# SCH_NeuroMems_V2_10_2025-06-07.net
KiCad netlist of a schematic drawn in EasyEDA
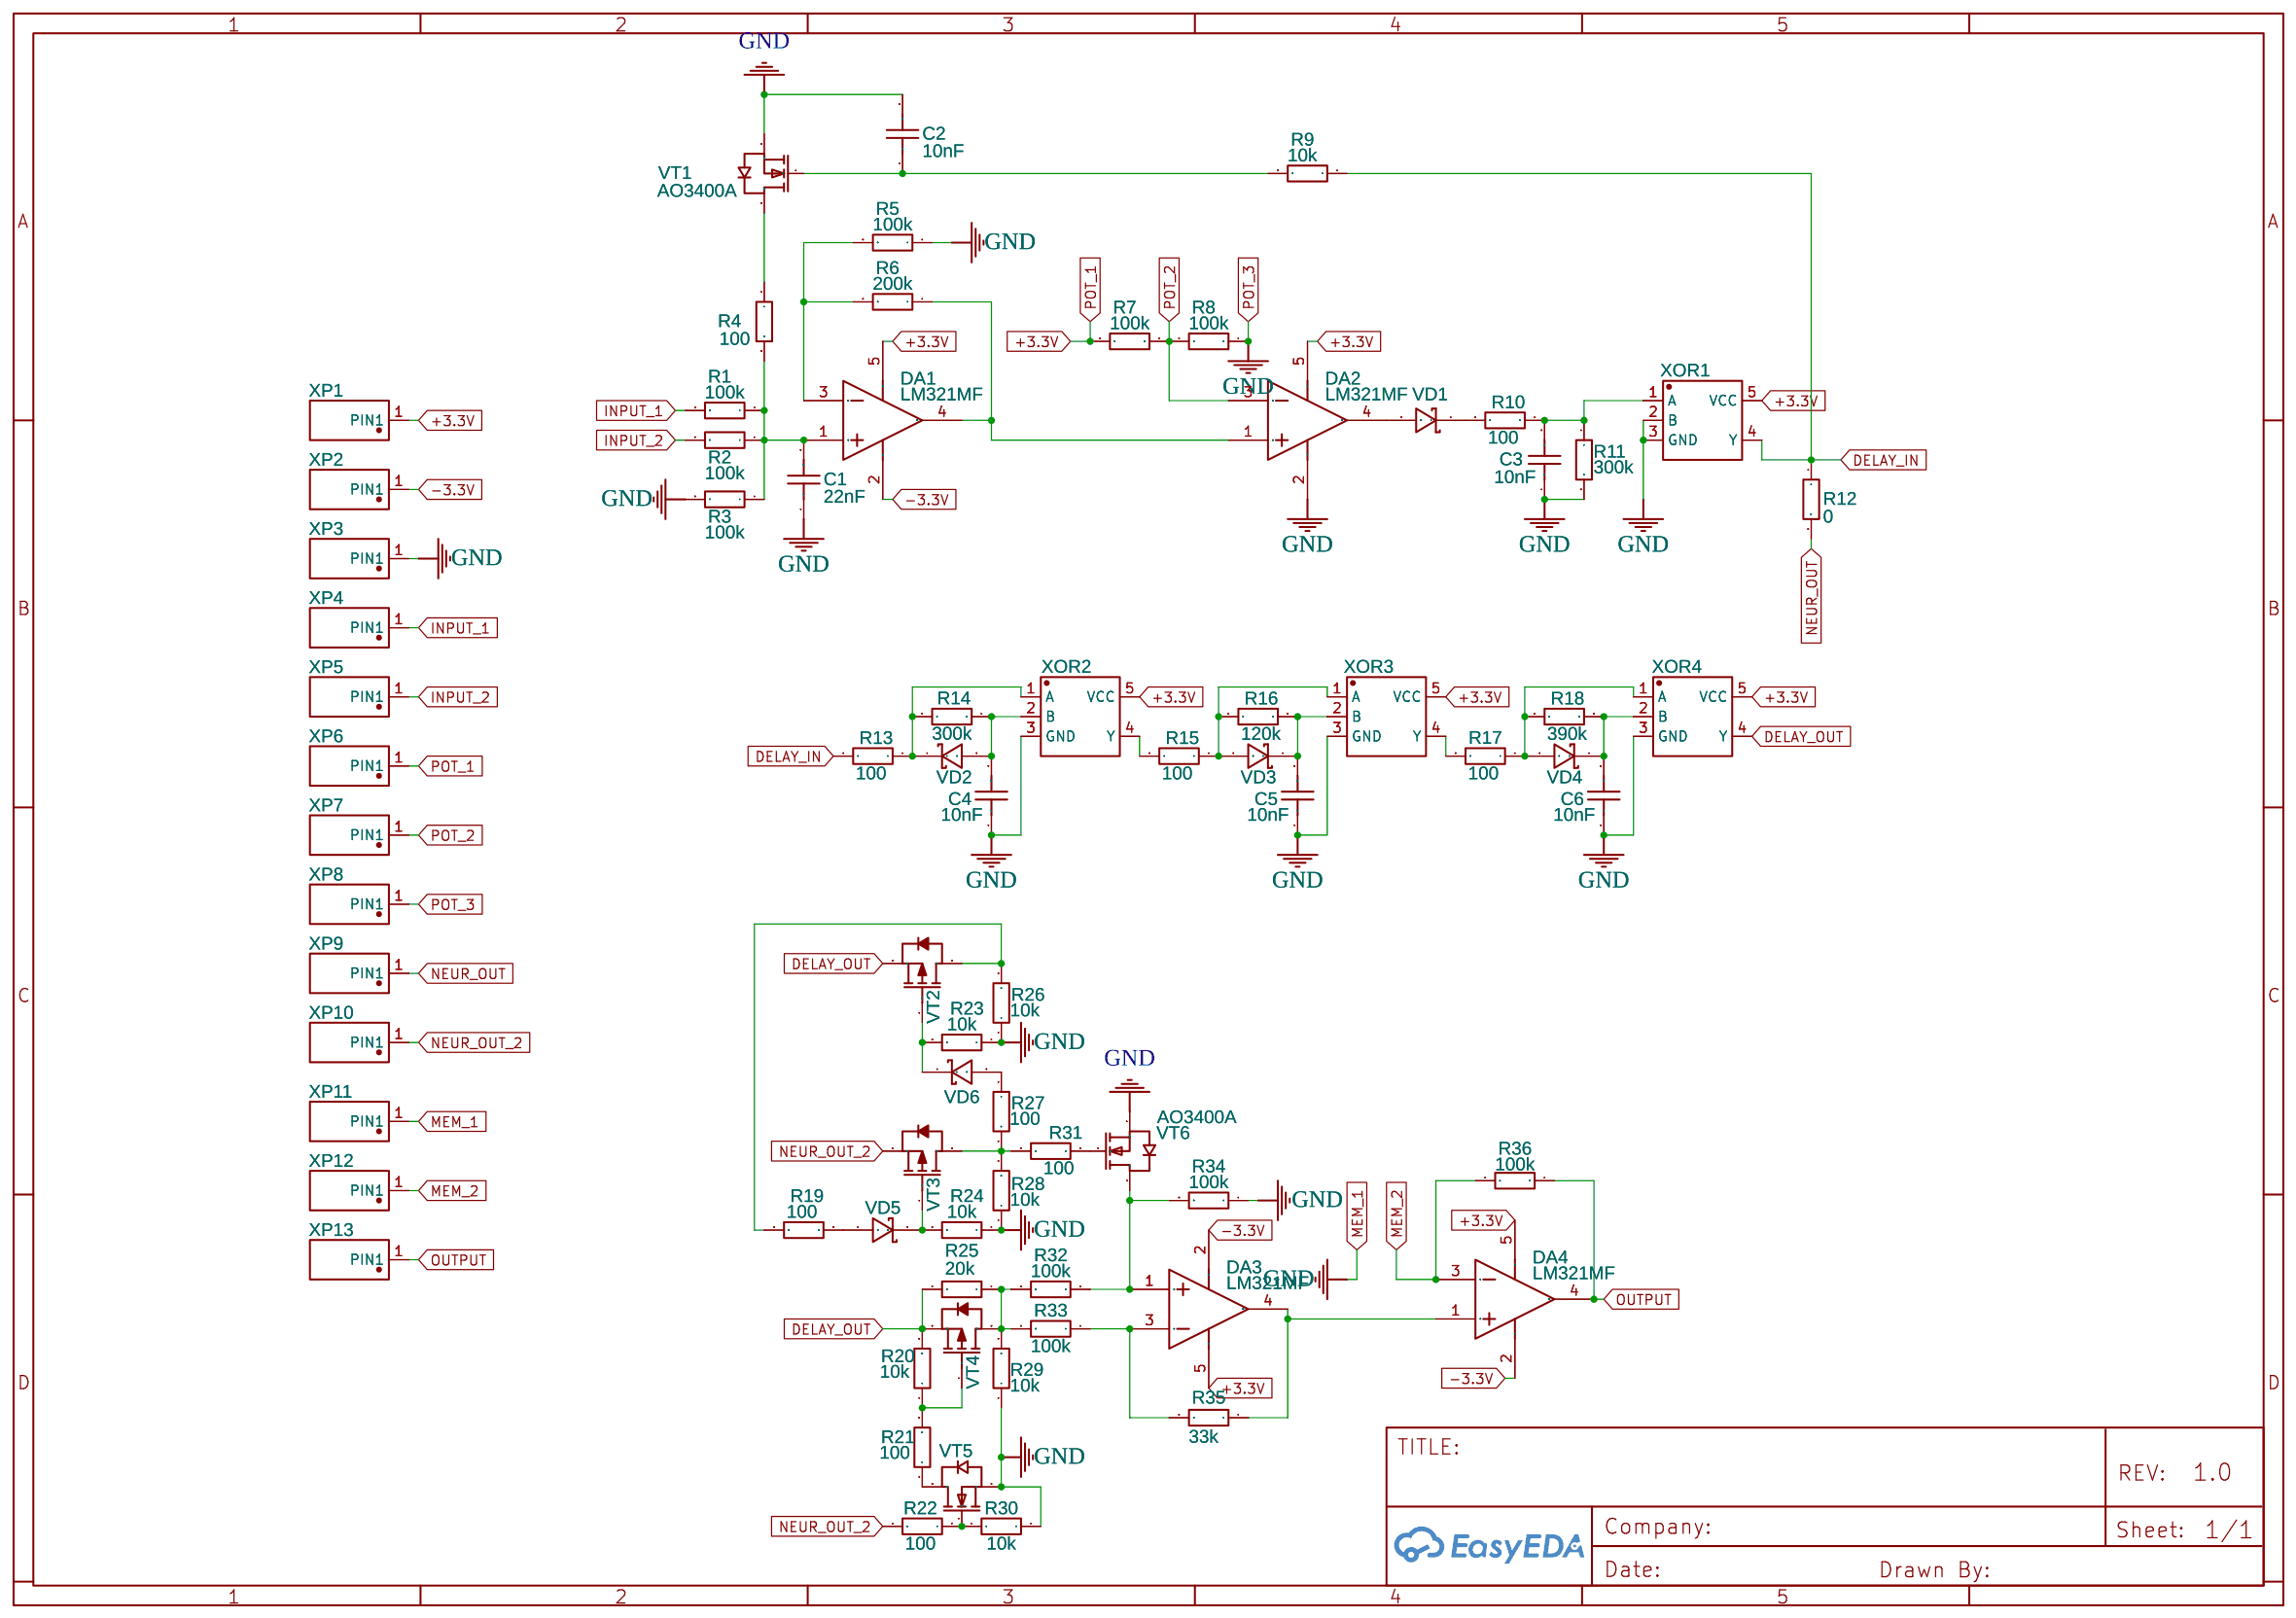
[diagram p0: schematic sheet]

(export (version "E")
  (design (tool "Eeschema 10.0.6"))
  (components
    (comp (ref "C1")
      (value "22nF")
      (fields (field (name "Manufacturer Part") "GRM155R71E103KA01D | SMD Ceramic Capacitor"))
      (libsource (lib "") (part "GRM155R71E103KA01D | SMD CERAMIC CAPACITOR"))
    )
    (comp (ref "C2")
      (value "10nF")
      (fields (field (name "Manufacturer Part") "0201"))
      (libsource (lib "") (part "0201_C9900015864"))
    )
    (comp (ref "C3")
      (value "10nF")
      (fields (field (name "Manufacturer Part") "GRM155R71E103KA01D | SMD Ceramic Capacitor"))
      (libsource (lib "") (part "GRM155R71E103KA01D | SMD CERAMIC CAPACITOR"))
    )
    (comp (ref "C4")
      (value "10nF")
      (fields (field (name "Manufacturer Part") "GRM155R71E103KA01D | SMD Ceramic Capacitor"))
      (libsource (lib "") (part "GRM155R71E103KA01D | SMD CERAMIC CAPACITOR"))
    )
    (comp (ref "C5")
      (value "10nF")
      (fields (field (name "Manufacturer Part") "GRM155R71E103KA01D | SMD Ceramic Capacitor"))
      (libsource (lib "") (part "GRM155R71E103KA01D | SMD CERAMIC CAPACITOR"))
    )
    (comp (ref "C6")
      (value "10nF")
      (fields (field (name "Manufacturer Part") "GRM155R71E103KA01D | SMD Ceramic Capacitor"))
      (libsource (lib "") (part "GRM155R71E103KA01D | SMD CERAMIC CAPACITOR"))
    )
    (comp (ref "DA1")
      (value "LM321MF")
      (fields (field (name "Manufacturer Part") "LM321MF/NOPB") (field (name "Manufacturer") "TI(德州仪器)"))
      (libsource (lib "") (part "LM321MF/NOPB"))
    )
    (comp (ref "DA2")
      (value "LM321MF")
      (fields (field (name "Manufacturer Part") "LM321MF/NOPB") (field (name "Manufacturer") "TI(德州仪器)"))
      (libsource (lib "") (part "LM321MF/NOPB"))
    )
    (comp (ref "DA3")
      (value "LM321MF")
      (fields (field (name "Manufacturer Part") "LM321MF/NOPB") (field (name "Manufacturer") "TI(德州仪器)"))
      (libsource (lib "") (part "LM321MF/NOPB_1"))
    )
    (comp (ref "DA4")
      (value "LM321MF")
      (fields (field (name "Manufacturer Part") "LM321MF/NOPB") (field (name "Manufacturer") "TI(德州仪器)"))
      (libsource (lib "") (part "LM321MF/NOPB"))
    )
    (comp (ref "R1")
      (value "100k")
      (fields (field (name "Manufacturer Part") "0201"))
      (libsource (lib "") (part "0201"))
    )
    (comp (ref "R2")
      (value "100k")
      (fields (field (name "Manufacturer Part") "0201"))
      (libsource (lib "") (part "0201"))
    )
    (comp (ref "R3")
      (value "100k")
      (fields (field (name "Manufacturer Part") "0201"))
      (libsource (lib "") (part "0201"))
    )
    (comp (ref "R4")
      (value "100")
      (fields (field (name "Manufacturer Part") "0201"))
      (libsource (lib "") (part "0201_3"))
    )
    (comp (ref "R5")
      (value "100k")
      (fields (field (name "Manufacturer Part") "0201"))
      (libsource (lib "") (part "0201"))
    )
    (comp (ref "R6")
      (value "200k")
      (fields (field (name "Manufacturer Part") "0201"))
      (libsource (lib "") (part "0201"))
    )
    (comp (ref "R7")
      (value "100k")
      (fields (field (name "Manufacturer Part") "0201"))
      (libsource (lib "") (part "0201"))
    )
    (comp (ref "R8")
      (value "100k")
      (fields (field (name "Manufacturer Part") "0201"))
      (libsource (lib "") (part "0201"))
    )
    (comp (ref "R9")
      (value "10k")
      (fields (field (name "Manufacturer Part") "0201"))
      (libsource (lib "") (part "0201"))
    )
    (comp (ref "R10")
      (value "100")
      (fields (field (name "Manufacturer Part") "0201"))
      (libsource (lib "") (part "0201"))
    )
    (comp (ref "R11")
      (value "300k")
      (fields (field (name "Manufacturer Part") "0201"))
      (libsource (lib "") (part "0201_3"))
    )
    (comp (ref "R12")
      (value "0")
      (fields (field (name "Manufacturer Part") "0201"))
      (libsource (lib "") (part "0201_3"))
    )
    (comp (ref "R13")
      (value "100")
      (fields (field (name "Manufacturer Part") "0201"))
      (libsource (lib "") (part "0201"))
    )
    (comp (ref "R14")
      (value "300k")
      (fields (field (name "Manufacturer Part") "0201"))
      (libsource (lib "") (part "0201"))
    )
    (comp (ref "R15")
      (value "100")
      (fields (field (name "Manufacturer Part") "0201"))
      (libsource (lib "") (part "0201"))
    )
    (comp (ref "R16")
      (value "120k")
      (fields (field (name "Manufacturer Part") "0201"))
      (libsource (lib "") (part "0201"))
    )
    (comp (ref "R17")
      (value "100")
      (fields (field (name "Manufacturer Part") "0201"))
      (libsource (lib "") (part "0201"))
    )
    (comp (ref "R18")
      (value "390k")
      (fields (field (name "Manufacturer Part") "0201"))
      (libsource (lib "") (part "0201"))
    )
    (comp (ref "R19")
      (value "100")
      (fields (field (name "Manufacturer Part") "0201"))
      (libsource (lib "") (part "0201_2"))
    )
    (comp (ref "R20")
      (value "10k")
      (fields (field (name "Manufacturer Part") "0201"))
      (libsource (lib "") (part "0201_1"))
    )
    (comp (ref "R21")
      (value "100")
      (fields (field (name "Manufacturer Part") "0201"))
      (libsource (lib "") (part "0201_1"))
    )
    (comp (ref "R22")
      (value "100")
      (fields (field (name "Manufacturer Part") "0201"))
      (libsource (lib "") (part "0201"))
    )
    (comp (ref "R23")
      (value "10k")
      (fields (field (name "Manufacturer Part") "0201"))
      (libsource (lib "") (part "0201"))
    )
    (comp (ref "R24")
      (value "10k")
      (fields (field (name "Manufacturer Part") "0201"))
      (libsource (lib "") (part "0201"))
    )
    (comp (ref "R25")
      (value "20k")
      (fields (field (name "Manufacturer Part") "0201"))
      (libsource (lib "") (part "0201"))
    )
    (comp (ref "R26")
      (value "10k")
      (fields (field (name "Manufacturer Part") "0201"))
      (libsource (lib "") (part "0201_1"))
    )
    (comp (ref "R27")
      (value "100")
      (fields (field (name "Manufacturer Part") "0201"))
      (libsource (lib "") (part "0201_3"))
    )
    (comp (ref "R28")
      (value "10k")
      (fields (field (name "Manufacturer Part") "0201"))
      (libsource (lib "") (part "0201_1"))
    )
    (comp (ref "R29")
      (value "10k")
      (fields (field (name "Manufacturer Part") "0201"))
      (libsource (lib "") (part "0201_1"))
    )
    (comp (ref "R30")
      (value "10k")
      (fields (field (name "Manufacturer Part") "0201"))
      (libsource (lib "") (part "0201"))
    )
    (comp (ref "R31")
      (value "100")
      (fields (field (name "Manufacturer Part") "0201"))
      (libsource (lib "") (part "0201_2"))
    )
    (comp (ref "R32")
      (value "100k")
      (fields (field (name "Manufacturer Part") "0201"))
      (libsource (lib "") (part "0201"))
    )
    (comp (ref "R33")
      (value "100k")
      (fields (field (name "Manufacturer Part") "0201"))
      (libsource (lib "") (part "0201"))
    )
    (comp (ref "R34")
      (value "100k")
      (fields (field (name "Manufacturer Part") "0201"))
      (libsource (lib "") (part "0201"))
    )
    (comp (ref "R35")
      (value "33k")
      (fields (field (name "Manufacturer Part") "0201"))
      (libsource (lib "") (part "0201"))
    )
    (comp (ref "R36")
      (value "100k")
      (fields (field (name "Manufacturer Part") "0201"))
      (libsource (lib "") (part "0201"))
    )
    (comp (ref "VD1")
      (value "1N5817WS")
      (fields (field (name "Manufacturer") "KEXIN(科信)"))
      (libsource (lib "") (part "1N5817WS"))
    )
    (comp (ref "VD2")
      (value "1N5817WS")
      (fields (field (name "Manufacturer") "KEXIN(科信)"))
      (libsource (lib "") (part "1N5817WS_1"))
    )
    (comp (ref "VD3")
      (value "1N5817WS")
      (fields (field (name "Manufacturer") "KEXIN(科信)"))
      (libsource (lib "") (part "1N5817WS"))
    )
    (comp (ref "VD4")
      (value "1N5817WS")
      (fields (field (name "Manufacturer") "KEXIN(科信)"))
      (libsource (lib "") (part "1N5817WS"))
    )
    (comp (ref "VD5")
      (value "1N5817WS")
      (fields (field (name "Manufacturer") "KEXIN(科信)"))
      (libsource (lib "") (part "1N5817WS"))
    )
    (comp (ref "VD6")
      (value "1N5817WS")
      (fields (field (name "Manufacturer") "KEXIN(科信)"))
      (libsource (lib "") (part "1N5817WS_1"))
    )
    (comp (ref "VT1")
      (value "AO3400A")
      (fields (field (name "Manufacturer") "BORN(伯恩半导体)"))
      (libsource (lib "") (part "AO3400A_C344010"))
    )
    (comp (ref "VT2")
      (value "AO3401A")
      (fields (field (name "Manufacturer") "AOS"))
      (libsource (lib "") (part "AO3401A"))
    )
    (comp (ref "VT3")
      (value "AO3401A")
      (fields (field (name "Manufacturer") "AOS"))
      (libsource (lib "") (part "AO3401A"))
    )
    (comp (ref "VT4")
      (value "AO3401A")
      (fields (field (name "Manufacturer") "AOS"))
      (libsource (lib "") (part "AO3401A"))
    )
    (comp (ref "VT5")
      (value "AO3400A")
      (fields (field (name "Manufacturer") "BORN(伯恩半导体)"))
      (libsource (lib "") (part "AO3400A_C344010_1"))
    )
    (comp (ref "VT6")
      (value "AO3400A")
      (fields (field (name "Manufacturer") "BORN(伯恩半导体)"))
      (libsource (lib "") (part "AO3400A_C344010_2"))
    )
    (comp (ref "XOR1")
      (value "SN74AHC1G86DBVR")
      (fields (field (name "Manufacturer") "TI(德州仪器)"))
      (libsource (lib "") (part "SN74AHC1G86DBVR"))
    )
    (comp (ref "XOR2")
      (value "SN74AHC1G86DBVR")
      (fields (field (name "Manufacturer") "TI(德州仪器)"))
      (libsource (lib "") (part "SN74AHC1G86DBVR"))
    )
    (comp (ref "XOR3")
      (value "SN74AHC1G86DBVR")
      (fields (field (name "Manufacturer") "TI(德州仪器)"))
      (libsource (lib "") (part "SN74AHC1G86DBVR"))
    )
    (comp (ref "XOR4")
      (value "SN74AHC1G86DBVR")
      (fields (field (name "Manufacturer") "TI(德州仪器)"))
      (libsource (lib "") (part "SN74AHC1G86DBVR"))
    )
    (comp (ref "XP1") (value "PLS-01 COPY") (libsource (lib "") (part "PLS-01 COPY")))
    (comp (ref "XP2") (value "PLS-01 COPY") (libsource (lib "") (part "PLS-01 COPY")))
    (comp (ref "XP3") (value "PLS-01 COPY") (libsource (lib "") (part "PLS-01 COPY")))
    (comp (ref "XP4") (value "PLS-01 COPY") (libsource (lib "") (part "PLS-01 COPY")))
    (comp (ref "XP5") (value "PLS-01 COPY") (libsource (lib "") (part "PLS-01 COPY")))
    (comp (ref "XP6") (value "PLS-01 COPY") (libsource (lib "") (part "PLS-01 COPY")))
    (comp (ref "XP7") (value "PLS-01 COPY") (libsource (lib "") (part "PLS-01 COPY")))
    (comp (ref "XP8") (value "PLS-01 COPY") (libsource (lib "") (part "PLS-01 COPY")))
    (comp (ref "XP9") (value "PLS-01 COPY") (libsource (lib "") (part "PLS-01 COPY")))
    (comp (ref "XP10") (value "PLS-01 COPY") (libsource (lib "") (part "PLS-01 COPY")))
    (comp (ref "XP11") (value "PLS-01 COPY") (libsource (lib "") (part "PLS-01 COPY")))
    (comp (ref "XP12") (value "PLS-01 COPY") (libsource (lib "") (part "PLS-01 COPY")))
    (comp (ref "XP13") (value "PLS-01 COPY") (libsource (lib "") (part "PLS-01 COPY")))
  )
  (nets
    (net (code "1") (name "+3.3V") (class "Default")
      (node (ref "DA1") (pin "5") (pinfunction "V+_5") (pintype "passive"))
      (node (ref "DA2") (pin "5") (pinfunction "V+_5") (pintype "passive"))
      (node (ref "DA3") (pin "5") (pinfunction "V+_5") (pintype "passive"))
      (node (ref "DA4") (pin "5") (pinfunction "V+_5") (pintype "passive"))
      (node (ref "R7") (pin "2") (pinfunction "2_2") (pintype "unspecified"))
      (node (ref "XOR1") (pin "5") (pinfunction "VCC_5") (pintype "unspecified"))
      (node (ref "XOR2") (pin "5") (pinfunction "VCC_5") (pintype "unspecified"))
      (node (ref "XOR3") (pin "5") (pinfunction "VCC_5") (pintype "unspecified"))
      (node (ref "XOR4") (pin "5") (pinfunction "VCC_5") (pintype "unspecified"))
      (node (ref "XP1") (pin "1") (pinfunction "PIN1_1") (pintype "unspecified"))
      (node (ref "XP6") (pin "1") (pinfunction "PIN1_1") (pintype "unspecified"))
    )
    (net (code "2") (name "-3.3V") (class "Default")
      (node (ref "DA1") (pin "2") (pinfunction "V-_2") (pintype "passive"))
      (node (ref "DA3") (pin "2") (pinfunction "V-_2") (pintype "passive"))
      (node (ref "DA4") (pin "2") (pinfunction "V-_2") (pintype "passive"))
      (node (ref "XP2") (pin "1") (pinfunction "PIN1_1") (pintype "unspecified"))
    )
    (net (code "3") (name "DELAY_IN") (class "Default")
      (node (ref "R12") (pin "1") (pinfunction "1_1") (pintype "unspecified"))
      (node (ref "R13") (pin "2") (pinfunction "2_2") (pintype "unspecified"))
      (node (ref "R9") (pin "1") (pinfunction "1_1") (pintype "unspecified"))
      (node (ref "XOR1") (pin "4") (pinfunction "Y_4") (pintype "unspecified"))
    )
    (net (code "4") (name "DELAY_OUT") (class "Default")
      (node (ref "R20") (pin "2") (pinfunction "2_2") (pintype "unspecified"))
      (node (ref "R25") (pin "2") (pinfunction "2_2") (pintype "unspecified"))
      (node (ref "VT2") (pin "2") (pinfunction "S_2") (pintype "unspecified"))
      (node (ref "VT4") (pin "2") (pinfunction "S_2") (pintype "unspecified"))
      (node (ref "XOR4") (pin "4") (pinfunction "Y_4") (pintype "unspecified"))
    )
    (net (code "5") (name "INPUT_1") (class "Default")
      (node (ref "R1") (pin "2") (pinfunction "2_2") (pintype "unspecified"))
      (node (ref "XP4") (pin "1") (pinfunction "PIN1_1") (pintype "unspecified"))
    )
    (net (code "6") (name "INPUT_2") (class "Default")
      (node (ref "R2") (pin "2") (pinfunction "2_2") (pintype "unspecified"))
      (node (ref "XP5") (pin "1") (pinfunction "PIN1_1") (pintype "unspecified"))
    )
    (net (code "7") (name "MEM_1") (class "Default")
      (node (ref "C1") (pin "1") (pinfunction "1_1") (pintype "unspecified"))
      (node (ref "C2") (pin "2") (pinfunction "2_2") (pintype "unspecified"))
      (node (ref "C3") (pin "1") (pinfunction "1_1") (pintype "unspecified"))
      (node (ref "C4") (pin "1") (pinfunction "1_1") (pintype "unspecified"))
      (node (ref "C5") (pin "1") (pinfunction "1_1") (pintype "unspecified"))
      (node (ref "C6") (pin "1") (pinfunction "1_1") (pintype "unspecified"))
      (node (ref "DA2") (pin "2") (pinfunction "V-_2") (pintype "passive"))
      (node (ref "R11") (pin "2") (pinfunction "2_2") (pintype "unspecified"))
      (node (ref "R23") (pin "1") (pinfunction "1_1") (pintype "unspecified"))
      (node (ref "R24") (pin "1") (pinfunction "1_1") (pintype "unspecified"))
      (node (ref "R26") (pin "1") (pinfunction "1_1") (pintype "unspecified"))
      (node (ref "R28") (pin "1") (pinfunction "1_1") (pintype "unspecified"))
      (node (ref "R29") (pin "1") (pinfunction "1_1") (pintype "unspecified"))
      (node (ref "R3") (pin "2") (pinfunction "2_2") (pintype "unspecified"))
      (node (ref "R30") (pin "1") (pinfunction "1_1") (pintype "unspecified"))
      (node (ref "R34") (pin "1") (pinfunction "1_1") (pintype "unspecified"))
      (node (ref "R5") (pin "1") (pinfunction "1_1") (pintype "unspecified"))
      (node (ref "R8") (pin "1") (pinfunction "1_1") (pintype "unspecified"))
      (node (ref "VT1") (pin "2") (pinfunction "S_2") (pintype "unspecified"))
      (node (ref "VT5") (pin "2") (pinfunction "S_2") (pintype "unspecified"))
      (node (ref "VT6") (pin "2") (pinfunction "S_2") (pintype "unspecified"))
      (node (ref "XOR1") (pin "2") (pinfunction "B_2") (pintype "unspecified"))
      (node (ref "XOR1") (pin "3") (pinfunction "GND_3") (pintype "unspecified"))
      (node (ref "XOR2") (pin "3") (pinfunction "GND_3") (pintype "unspecified"))
      (node (ref "XOR3") (pin "3") (pinfunction "GND_3") (pintype "unspecified"))
      (node (ref "XOR4") (pin "3") (pinfunction "GND_3") (pintype "unspecified"))
      (node (ref "XP11") (pin "1") (pinfunction "PIN1_1") (pintype "unspecified"))
      (node (ref "XP3") (pin "1") (pinfunction "PIN1_1") (pintype "unspecified"))
      (node (ref "XP8") (pin "1") (pinfunction "PIN1_1") (pintype "unspecified"))
    )
    (net (code "8") (name "MEM_2") (class "Default")
      (node (ref "DA4") (pin "3") (pinfunction "IN-_3") (pintype "unspecified"))
      (node (ref "R36") (pin "2") (pinfunction "2_2") (pintype "unspecified"))
      (node (ref "XP12") (pin "1") (pinfunction "PIN1_1") (pintype "unspecified"))
    )
    (net (code "9") (name "NEUR_OUT") (class "Default")
      (node (ref "R12") (pin "2") (pinfunction "2_2") (pintype "unspecified"))
      (node (ref "XP9") (pin "1") (pinfunction "PIN1_1") (pintype "unspecified"))
    )
    (net (code "10") (name "NEUR_OUT_2") (class "Default")
      (node (ref "R22") (pin "2") (pinfunction "2_2") (pintype "unspecified"))
      (node (ref "VT3") (pin "2") (pinfunction "S_2") (pintype "unspecified"))
      (node (ref "XP10") (pin "1") (pinfunction "PIN1_1") (pintype "unspecified"))
    )
    (net (code "11") (name "Net-(DA1-IN+)") (class "Default")
      (node (ref "C1") (pin "2") (pinfunction "2_2") (pintype "unspecified"))
      (node (ref "DA1") (pin "1") (pinfunction "IN+_1") (pintype "unspecified"))
      (node (ref "R1") (pin "1") (pinfunction "1_1") (pintype "unspecified"))
      (node (ref "R2") (pin "1") (pinfunction "1_1") (pintype "unspecified"))
      (node (ref "R3") (pin "1") (pinfunction "1_1") (pintype "unspecified"))
      (node (ref "R4") (pin "2") (pinfunction "2_2") (pintype "unspecified"))
    )
    (net (code "12") (name "Net-(DA1-IN-)") (class "Default")
      (node (ref "DA1") (pin "3") (pinfunction "IN-_3") (pintype "unspecified"))
      (node (ref "R5") (pin "2") (pinfunction "2_2") (pintype "unspecified"))
      (node (ref "R6") (pin "2") (pinfunction "2_2") (pintype "unspecified"))
    )
    (net (code "13") (name "Net-(DA1-OUT)") (class "Default")
      (node (ref "DA1") (pin "4") (pinfunction "OUT_4") (pintype "output"))
      (node (ref "DA2") (pin "1") (pinfunction "IN+_1") (pintype "unspecified"))
      (node (ref "R6") (pin "1") (pinfunction "1_1") (pintype "unspecified"))
    )
    (net (code "14") (name "Net-(DA2-OUT)") (class "Default")
      (node (ref "DA2") (pin "4") (pinfunction "OUT_4") (pintype "output"))
      (node (ref "VD1") (pin "2") (pinfunction "2_2") (pintype "unspecified"))
    )
    (net (code "15") (name "Net-(DA3-IN+)") (class "Default")
      (node (ref "DA3") (pin "1") (pinfunction "IN+_1") (pintype "unspecified"))
      (node (ref "R32") (pin "1") (pinfunction "1_1") (pintype "unspecified"))
      (node (ref "R34") (pin "2") (pinfunction "2_2") (pintype "unspecified"))
      (node (ref "VT6") (pin "3") (pinfunction "D_3") (pintype "unspecified"))
    )
    (net (code "16") (name "Net-(DA3-IN-)") (class "Default")
      (node (ref "DA3") (pin "3") (pinfunction "IN-_3") (pintype "unspecified"))
      (node (ref "R33") (pin "1") (pinfunction "1_1") (pintype "unspecified"))
      (node (ref "R35") (pin "2") (pinfunction "2_2") (pintype "unspecified"))
    )
    (net (code "17") (name "Net-(DA3-OUT)") (class "Default")
      (node (ref "DA3") (pin "4") (pinfunction "OUT_4") (pintype "output"))
      (node (ref "DA4") (pin "1") (pinfunction "IN+_1") (pintype "unspecified"))
      (node (ref "R35") (pin "1") (pinfunction "1_1") (pintype "unspecified"))
    )
    (net (code "18") (name "Net-(R10-Pad2)") (class "Default")
      (node (ref "R10") (pin "2") (pinfunction "2_2") (pintype "unspecified"))
      (node (ref "VD1") (pin "1") (pinfunction "1_1") (pintype "unspecified"))
    )
    (net (code "19") (name "Net-(R19-Pad2)") (class "Default")
      (node (ref "R19") (pin "2") (pinfunction "2_2") (pintype "unspecified"))
      (node (ref "VD5") (pin "2") (pinfunction "2_2") (pintype "unspecified"))
    )
    (net (code "20") (name "Net-(R27-Pad1)") (class "Default")
      (node (ref "R27") (pin "1") (pinfunction "1_1") (pintype "unspecified"))
      (node (ref "VD6") (pin "2") (pinfunction "2_2") (pintype "unspecified"))
    )
    (net (code "21") (name "Net-(VT1-D)") (class "Default")
      (node (ref "R4") (pin "1") (pinfunction "1_1") (pintype "unspecified"))
      (node (ref "VT1") (pin "3") (pinfunction "D_3") (pintype "unspecified"))
    )
    (net (code "22") (name "Net-(VT1-G)") (class "Default")
      (node (ref "C2") (pin "1") (pinfunction "1_1") (pintype "unspecified"))
      (node (ref "R9") (pin "2") (pinfunction "2_2") (pintype "unspecified"))
      (node (ref "VT1") (pin "1") (pinfunction "G_1") (pintype "unspecified"))
    )
    (net (code "23") (name "Net-(VT2-D)") (class "Default")
      (node (ref "R19") (pin "1") (pinfunction "1_1") (pintype "unspecified"))
      (node (ref "R26") (pin "2") (pinfunction "2_2") (pintype "unspecified"))
      (node (ref "VT2") (pin "3") (pinfunction "D_3") (pintype "unspecified"))
    )
    (net (code "24") (name "Net-(VT2-G)") (class "Default")
      (node (ref "R23") (pin "2") (pinfunction "2_2") (pintype "unspecified"))
      (node (ref "VD6") (pin "1") (pinfunction "1_1") (pintype "unspecified"))
      (node (ref "VT2") (pin "1") (pinfunction "G_1") (pintype "unspecified"))
    )
    (net (code "25") (name "Net-(VT3-D)") (class "Default")
      (node (ref "R27") (pin "2") (pinfunction "2_2") (pintype "unspecified"))
      (node (ref "R28") (pin "2") (pinfunction "2_2") (pintype "unspecified"))
      (node (ref "R31") (pin "1") (pinfunction "1_1") (pintype "unspecified"))
      (node (ref "VT3") (pin "3") (pinfunction "D_3") (pintype "unspecified"))
    )
    (net (code "26") (name "Net-(VT3-G)") (class "Default")
      (node (ref "R24") (pin "2") (pinfunction "2_2") (pintype "unspecified"))
      (node (ref "VD5") (pin "1") (pinfunction "1_1") (pintype "unspecified"))
      (node (ref "VT3") (pin "1") (pinfunction "G_1") (pintype "unspecified"))
    )
    (net (code "27") (name "Net-(VT4-D)") (class "Default")
      (node (ref "R25") (pin "1") (pinfunction "1_1") (pintype "unspecified"))
      (node (ref "R29") (pin "2") (pinfunction "2_2") (pintype "unspecified"))
      (node (ref "R32") (pin "2") (pinfunction "2_2") (pintype "unspecified"))
      (node (ref "R33") (pin "2") (pinfunction "2_2") (pintype "unspecified"))
      (node (ref "VT4") (pin "3") (pinfunction "D_3") (pintype "unspecified"))
    )
    (net (code "28") (name "Net-(VT4-G)") (class "Default")
      (node (ref "R20") (pin "1") (pinfunction "1_1") (pintype "unspecified"))
      (node (ref "R21") (pin "2") (pinfunction "2_2") (pintype "unspecified"))
      (node (ref "VT4") (pin "1") (pinfunction "G_1") (pintype "unspecified"))
    )
    (net (code "29") (name "Net-(VT5-D)") (class "Default")
      (node (ref "R21") (pin "1") (pinfunction "1_1") (pintype "unspecified"))
      (node (ref "VT5") (pin "3") (pinfunction "D_3") (pintype "unspecified"))
    )
    (net (code "30") (name "Net-(VT5-G)") (class "Default")
      (node (ref "R22") (pin "1") (pinfunction "1_1") (pintype "unspecified"))
      (node (ref "R30") (pin "2") (pinfunction "2_2") (pintype "unspecified"))
      (node (ref "VT5") (pin "1") (pinfunction "G_1") (pintype "unspecified"))
    )
    (net (code "31") (name "Net-(VT6-G)") (class "Default")
      (node (ref "R31") (pin "2") (pinfunction "2_2") (pintype "unspecified"))
      (node (ref "VT6") (pin "1") (pinfunction "G_1") (pintype "unspecified"))
    )
    (net (code "32") (name "Net-(XOR1-A)") (class "Default")
      (node (ref "C3") (pin "2") (pinfunction "2_2") (pintype "unspecified"))
      (node (ref "R10") (pin "1") (pinfunction "1_1") (pintype "unspecified"))
      (node (ref "R11") (pin "1") (pinfunction "1_1") (pintype "unspecified"))
      (node (ref "XOR1") (pin "1") (pinfunction "A_1") (pintype "unspecified"))
    )
    (net (code "33") (name "Net-(XOR2-A)") (class "Default")
      (node (ref "R13") (pin "1") (pinfunction "1_1") (pintype "unspecified"))
      (node (ref "R14") (pin "2") (pinfunction "2_2") (pintype "unspecified"))
      (node (ref "VD2") (pin "1") (pinfunction "1_1") (pintype "unspecified"))
      (node (ref "XOR2") (pin "1") (pinfunction "A_1") (pintype "unspecified"))
    )
    (net (code "34") (name "Net-(XOR2-B)") (class "Default")
      (node (ref "C4") (pin "2") (pinfunction "2_2") (pintype "unspecified"))
      (node (ref "R14") (pin "1") (pinfunction "1_1") (pintype "unspecified"))
      (node (ref "VD2") (pin "2") (pinfunction "2_2") (pintype "unspecified"))
      (node (ref "XOR2") (pin "2") (pinfunction "B_2") (pintype "unspecified"))
    )
    (net (code "35") (name "Net-(XOR2-Y)") (class "Default")
      (node (ref "R15") (pin "2") (pinfunction "2_2") (pintype "unspecified"))
      (node (ref "XOR2") (pin "4") (pinfunction "Y_4") (pintype "unspecified"))
    )
    (net (code "36") (name "Net-(XOR3-A)") (class "Default")
      (node (ref "R15") (pin "1") (pinfunction "1_1") (pintype "unspecified"))
      (node (ref "R16") (pin "2") (pinfunction "2_2") (pintype "unspecified"))
      (node (ref "VD3") (pin "2") (pinfunction "2_2") (pintype "unspecified"))
      (node (ref "XOR3") (pin "1") (pinfunction "A_1") (pintype "unspecified"))
    )
    (net (code "37") (name "Net-(XOR3-B)") (class "Default")
      (node (ref "C5") (pin "2") (pinfunction "2_2") (pintype "unspecified"))
      (node (ref "R16") (pin "1") (pinfunction "1_1") (pintype "unspecified"))
      (node (ref "VD3") (pin "1") (pinfunction "1_1") (pintype "unspecified"))
      (node (ref "XOR3") (pin "2") (pinfunction "B_2") (pintype "unspecified"))
    )
    (net (code "38") (name "Net-(XOR3-Y)") (class "Default")
      (node (ref "R17") (pin "2") (pinfunction "2_2") (pintype "unspecified"))
      (node (ref "XOR3") (pin "4") (pinfunction "Y_4") (pintype "unspecified"))
    )
    (net (code "39") (name "Net-(XOR4-A)") (class "Default")
      (node (ref "R17") (pin "1") (pinfunction "1_1") (pintype "unspecified"))
      (node (ref "R18") (pin "2") (pinfunction "2_2") (pintype "unspecified"))
      (node (ref "VD4") (pin "2") (pinfunction "2_2") (pintype "unspecified"))
      (node (ref "XOR4") (pin "1") (pinfunction "A_1") (pintype "unspecified"))
    )
    (net (code "40") (name "Net-(XOR4-B)") (class "Default")
      (node (ref "C6") (pin "2") (pinfunction "2_2") (pintype "unspecified"))
      (node (ref "R18") (pin "1") (pinfunction "1_1") (pintype "unspecified"))
      (node (ref "VD4") (pin "1") (pinfunction "1_1") (pintype "unspecified"))
      (node (ref "XOR4") (pin "2") (pinfunction "B_2") (pintype "unspecified"))
    )
    (net (code "41") (name "OUTPUT") (class "Default")
      (node (ref "DA4") (pin "4") (pinfunction "OUT_4") (pintype "output"))
      (node (ref "R36") (pin "1") (pinfunction "1_1") (pintype "unspecified"))
      (node (ref "XP13") (pin "1") (pinfunction "PIN1_1") (pintype "unspecified"))
    )
    (net (code "42") (name "POT_2") (class "Default")
      (node (ref "DA2") (pin "3") (pinfunction "IN-_3") (pintype "unspecified"))
      (node (ref "R7") (pin "1") (pinfunction "1_1") (pintype "unspecified"))
      (node (ref "R8") (pin "2") (pinfunction "2_2") (pintype "unspecified"))
      (node (ref "XP7") (pin "1") (pinfunction "PIN1_1") (pintype "unspecified"))
    )
  )
)
